# VTTVREF.net
KiCad netlist of a schematic drawn in Altium Designer
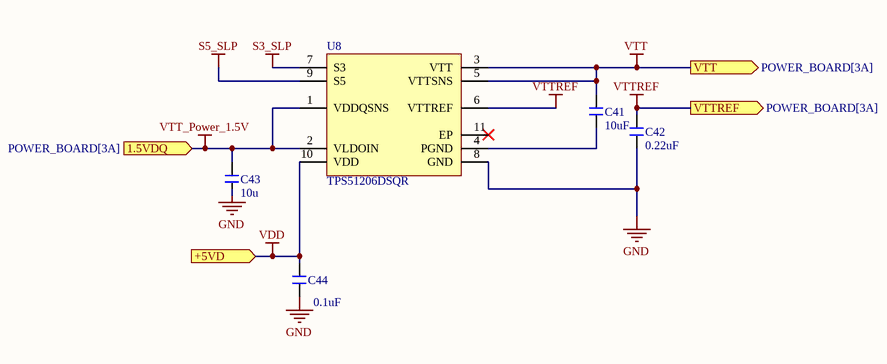
[diagram p0: VTTVREF.SchDoc]

(export (version "E")
  (design (tool "Eeschema 10.0.6"))
  (components
    (comp (ref "C41")
      (value "10uF")
      (footprint "C 0805_L")
      (description "贴片电容 10 µF, 6.3 V, X5R, 1608 (0603),  JMK107BJ106MA")
      (libsource (lib "0.1 - 电阻-电容-电感") (part "C"))
    )
    (comp (ref "C42")
      (value "0.22uF")
      (footprint "C 0805_L")
      (description "贴片电容 C4 0.22 µF, 6.3 V, X5R, 1005 (0402) Taiyo Yuden JMK105BJ224KV")
      (libsource (lib "0.1 - 电阻-电容-电感") (part "C"))
    )
    (comp (ref "C43")
      (value "10u")
      (footprint "C 0805_L")
      (description "贴片电容 10 µF, 6.3 V, X5R, 1608 (0603) Taiyo Yuden JMK107BJ106MA")
      (libsource (lib "0.1 - 电阻-电容-电感") (part "C"))
    )
    (comp (ref "C44")
      (value "0.1uF")
      (footprint "C 0805_L")
      (description "贴片电容 0.1 µF, 6.3 V, X5R, 1005 (0402) Taiyo Yuden JWK105BJ104MP")
      (libsource (lib "0.1 - 电阻-电容-电感") (part "C"))
    )
    (comp (ref "U8")
      (value "TPS51206DSQR")
      (footprint "DSQ0010A_V")
      (fields (field (name "MANUFACTURER") "Texas Instruments"))
      (libsource (lib "Components - 23.10.23 - 13.51") (part "CMP-0395-00678-2"))
    )
  )
  (nets
    (net (code "1") (name "GND") (class "Default")
      (node (ref "C42") (pin "1") (pinfunction "1_1") (pintype "passive"))
      (node (ref "C43") (pin "1") (pinfunction "1_1") (pintype "passive"))
      (node (ref "C44") (pin "1") (pinfunction "1_1") (pintype "passive"))
      (node (ref "U8") (pin "8") (pinfunction "GND_8") (pintype "power_in"))
    )
    (net (code "2") (name "Net-(U8-PGND)") (class "Default")
      (node (ref "C41") (pin "1") (pinfunction "1_1") (pintype "passive"))
      (node (ref "U8") (pin "4") (pinfunction "PGND_4") (pintype "power_in"))
    )
    (net (code "3") (name "S3_SLP") (class "Default")
      (node (ref "U8") (pin "7") (pinfunction "S3_7") (pintype "passive"))
    )
    (net (code "4") (name "S5_SLP") (class "Default")
      (node (ref "U8") (pin "9") (pinfunction "S5_9") (pintype "passive"))
    )
    (net (code "5") (name "VDD") (class "Default")
      (node (ref "C44") (pin "2") (pinfunction "2_2") (pintype "passive"))
      (node (ref "U8") (pin "10") (pinfunction "VDD_10") (pintype "passive"))
    )
    (net (code "6") (name "VTT") (class "Default")
      (node (ref "C41") (pin "2") (pinfunction "2_2") (pintype "passive"))
      (node (ref "U8") (pin "3") (pinfunction "VTT_3") (pintype "power_in"))
      (node (ref "U8") (pin "5") (pinfunction "VTTSNS_5") (pintype "passive"))
    )
    (net (code "7") (name "VTTREF") (class "Default")
      (node (ref "C42") (pin "2") (pinfunction "2_2") (pintype "passive"))
      (node (ref "U8") (pin "6") (pinfunction "VTTREF_6") (pintype "passive"))
    )
    (net (code "8") (name "VTT_Power_1.5V") (class "Default")
      (node (ref "C43") (pin "2") (pinfunction "2_2") (pintype "passive"))
      (node (ref "U8") (pin "1") (pinfunction "VDDQSNS_1") (pintype "passive"))
      (node (ref "U8") (pin "2") (pinfunction "VLDOIN_2") (pintype "passive"))
    )
    (net (code "9") (name "unconnected-(U8-EP-Pad11)") (class "Default")
      (node (ref "U8") (pin "11") (pinfunction "EP_11") (pintype "power_in+no_connect"))
    )
  )
)
